# Sheet1.net
KiCad netlist of a schematic drawn in Altium Designer
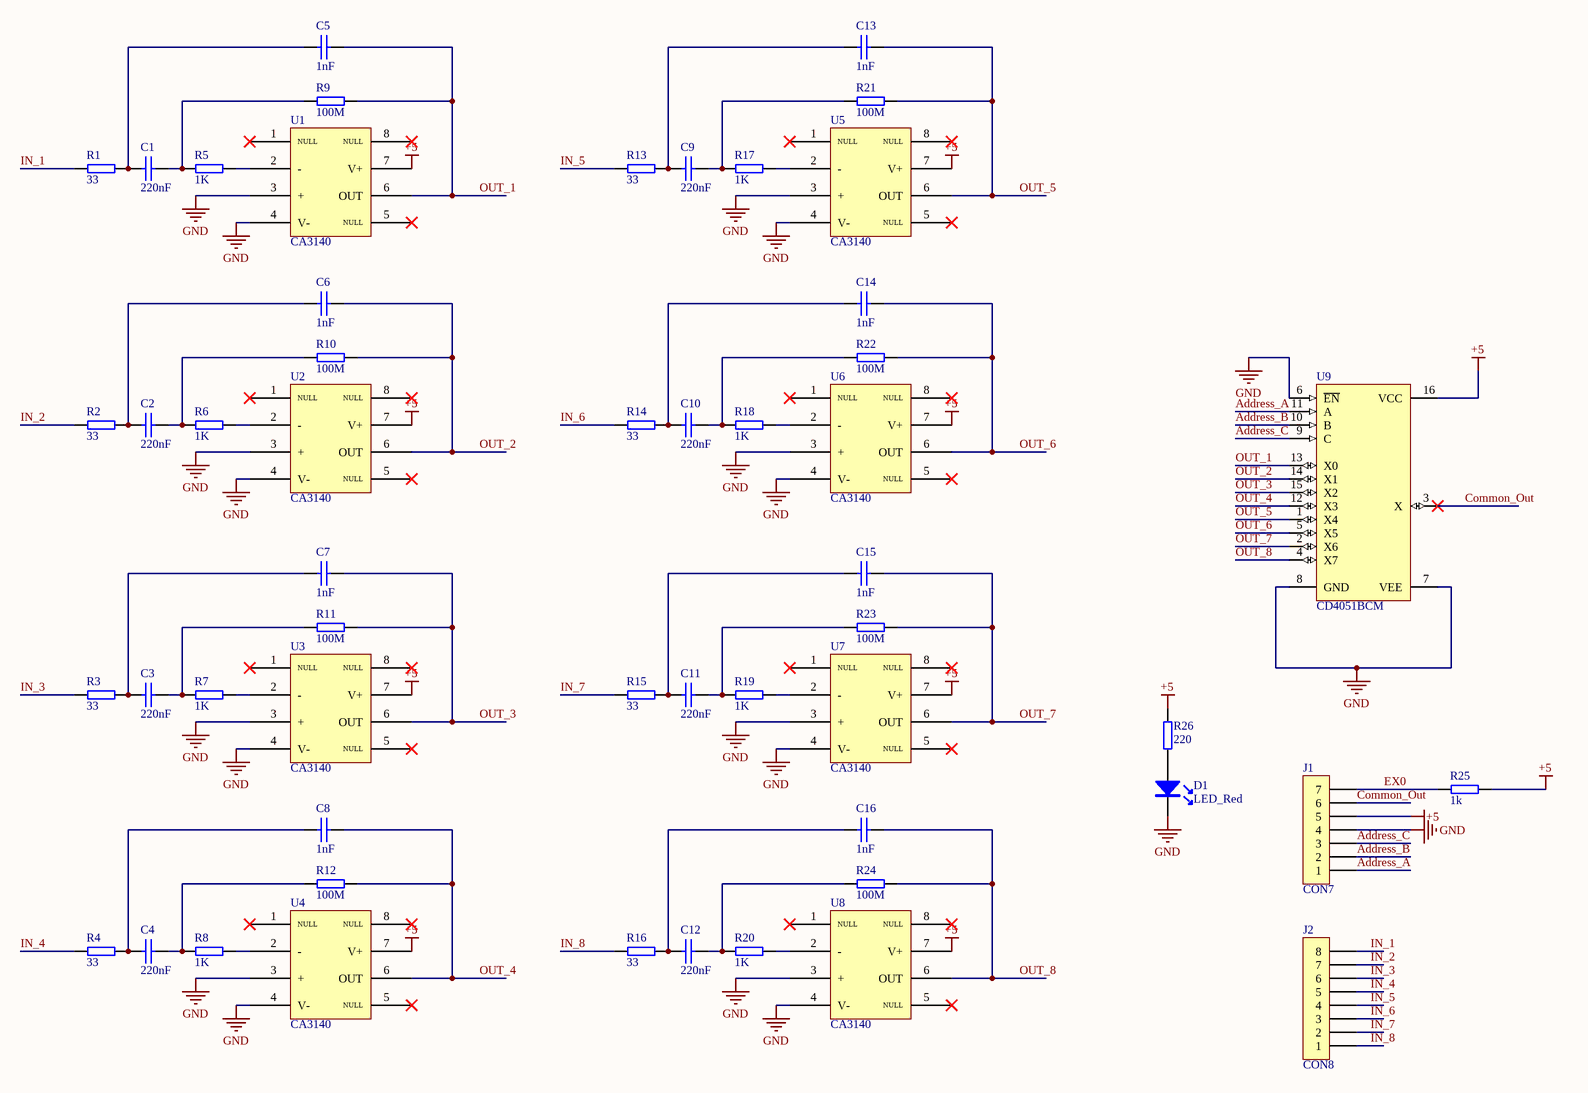
[diagram p0: Sheet1.SchDoc]

(export (version "E")
  (design (tool "Eeschema 10.0.6"))
  (components
    (comp (ref "C1")
      (value "220nF")
      (footprint "6-0805_L")
      (description "电容")
      (libsource (lib "Component") (part "CAP"))
    )
    (comp (ref "C2")
      (value "220nF")
      (footprint "6-0805_L")
      (description "电容")
      (libsource (lib "Component") (part "CAP"))
    )
    (comp (ref "C3")
      (value "220nF")
      (footprint "6-0805_L")
      (description "电容")
      (libsource (lib "Component") (part "CAP"))
    )
    (comp (ref "C4")
      (value "220nF")
      (footprint "6-0805_L")
      (description "电容")
      (libsource (lib "Component") (part "CAP"))
    )
    (comp (ref "C5")
      (value "1nF")
      (footprint "6-0805_L")
      (description "电容")
      (libsource (lib "Component") (part "CAP"))
    )
    (comp (ref "C6")
      (value "1nF")
      (footprint "6-0805_L")
      (description "电容")
      (libsource (lib "Component") (part "CAP"))
    )
    (comp (ref "C7")
      (value "1nF")
      (footprint "6-0805_L")
      (description "电容")
      (libsource (lib "Component") (part "CAP"))
    )
    (comp (ref "C8")
      (value "1nF")
      (footprint "6-0805_L")
      (description "电容")
      (libsource (lib "Component") (part "CAP"))
    )
    (comp (ref "C9")
      (value "220nF")
      (footprint "6-0805_L")
      (description "电容")
      (libsource (lib "Component") (part "CAP"))
    )
    (comp (ref "C10")
      (value "220nF")
      (footprint "6-0805_L")
      (description "电容")
      (libsource (lib "Component") (part "CAP"))
    )
    (comp (ref "C11")
      (value "220nF")
      (footprint "6-0805_L")
      (description "电容")
      (libsource (lib "Component") (part "CAP"))
    )
    (comp (ref "C12")
      (value "220nF")
      (footprint "6-0805_L")
      (description "电容")
      (libsource (lib "Component") (part "CAP"))
    )
    (comp (ref "C13")
      (value "1nF")
      (footprint "6-0805_L")
      (description "电容")
      (libsource (lib "Component") (part "CAP"))
    )
    (comp (ref "C14")
      (value "1nF")
      (footprint "6-0805_L")
      (description "电容")
      (libsource (lib "Component") (part "CAP"))
    )
    (comp (ref "C15")
      (value "1nF")
      (footprint "6-0805_L")
      (description "电容")
      (libsource (lib "Component") (part "CAP"))
    )
    (comp (ref "C16")
      (value "1nF")
      (footprint "6-0805_L")
      (description "电容")
      (libsource (lib "Component") (part "CAP"))
    )
    (comp (ref "D1")
      (value "LED_Red")
      (footprint "6-0805_M")
      (description "LED")
      (libsource (lib "Component") (part "LED"))
    )
    (comp (ref "J1")
      (value "CON7")
      (footprint "HDR1X7")
      (description "Connector")
      (libsource (lib "杂元件库") (part "CON7"))
    )
    (comp (ref "J2")
      (value "CON8")
      (footprint "XH2.54-8P")
      (description "连接器")
      (libsource (lib "Connector") (part "CON8"))
    )
    (comp (ref "R1")
      (value "33")
      (footprint "Miscellaneous Devices:6-0805_M")
      (description "电阻")
      (libsource (lib "Component") (part "RES"))
    )
    (comp (ref "R2")
      (value "33")
      (footprint "Miscellaneous Devices:6-0805_M")
      (description "电阻")
      (libsource (lib "Component") (part "RES"))
    )
    (comp (ref "R3")
      (value "33")
      (footprint "Miscellaneous Devices:6-0805_M")
      (description "电阻")
      (libsource (lib "Component") (part "RES"))
    )
    (comp (ref "R4")
      (value "33")
      (footprint "Miscellaneous Devices:6-0805_M")
      (description "电阻")
      (libsource (lib "Component") (part "RES"))
    )
    (comp (ref "R5")
      (value "1K")
      (footprint "6-0805_M")
      (description "电阻")
      (libsource (lib "Component") (part "RES"))
    )
    (comp (ref "R6")
      (value "1K")
      (footprint "6-0805_M")
      (description "电阻")
      (libsource (lib "Component") (part "RES"))
    )
    (comp (ref "R7")
      (value "1K")
      (footprint "6-0805_M")
      (description "电阻")
      (libsource (lib "Component") (part "RES"))
    )
    (comp (ref "R8")
      (value "1K")
      (footprint "6-0805_M")
      (description "电阻")
      (libsource (lib "Component") (part "RES"))
    )
    (comp (ref "R9")
      (value "100M")
      (footprint "Miscellaneous Devices:6-0805_M")
      (description "电阻")
      (libsource (lib "Component") (part "RES"))
    )
    (comp (ref "R10")
      (value "100M")
      (footprint "Miscellaneous Devices:6-0805_M")
      (description "电阻")
      (libsource (lib "Component") (part "RES"))
    )
    (comp (ref "R11")
      (value "100M")
      (footprint "Miscellaneous Devices:6-0805_M")
      (description "电阻")
      (libsource (lib "Component") (part "RES"))
    )
    (comp (ref "R12")
      (value "100M")
      (footprint "Miscellaneous Devices:6-0805_M")
      (description "电阻")
      (libsource (lib "Component") (part "RES"))
    )
    (comp (ref "R13")
      (value "33")
      (footprint "Miscellaneous Devices:6-0805_M")
      (description "电阻")
      (libsource (lib "Component") (part "RES"))
    )
    (comp (ref "R14")
      (value "33")
      (footprint "Miscellaneous Devices:6-0805_M")
      (description "电阻")
      (libsource (lib "Component") (part "RES"))
    )
    (comp (ref "R15")
      (value "33")
      (footprint "Miscellaneous Devices:6-0805_M")
      (description "电阻")
      (libsource (lib "Component") (part "RES"))
    )
    (comp (ref "R16")
      (value "33")
      (footprint "Miscellaneous Devices:6-0805_M")
      (description "电阻")
      (libsource (lib "Component") (part "RES"))
    )
    (comp (ref "R17")
      (value "1K")
      (footprint "6-0805_M")
      (description "电阻")
      (libsource (lib "Component") (part "RES"))
    )
    (comp (ref "R18")
      (value "1K")
      (footprint "6-0805_M")
      (description "电阻")
      (libsource (lib "Component") (part "RES"))
    )
    (comp (ref "R19")
      (value "1K")
      (footprint "6-0805_M")
      (description "电阻")
      (libsource (lib "Component") (part "RES"))
    )
    (comp (ref "R20")
      (value "1K")
      (footprint "6-0805_M")
      (description "电阻")
      (libsource (lib "Component") (part "RES"))
    )
    (comp (ref "R21")
      (value "100M")
      (footprint "Miscellaneous Devices:6-0805_M")
      (description "电阻")
      (libsource (lib "Component") (part "RES"))
    )
    (comp (ref "R22")
      (value "100M")
      (footprint "Miscellaneous Devices:6-0805_M")
      (description "电阻")
      (libsource (lib "Component") (part "RES"))
    )
    (comp (ref "R23")
      (value "100M")
      (footprint "Miscellaneous Devices:6-0805_M")
      (description "电阻")
      (libsource (lib "Component") (part "RES"))
    )
    (comp (ref "R24")
      (value "100M")
      (footprint "Miscellaneous Devices:6-0805_M")
      (description "电阻")
      (libsource (lib "Component") (part "RES"))
    )
    (comp (ref "R25")
      (value "1k")
      (footprint "6-0805_M")
      (description "电阻")
      (libsource (lib "Component") (part "RES"))
    )
    (comp (ref "R26")
      (value "220")
      (footprint "6-0805_M")
      (description "电阻")
      (libsource (lib "Component") (part "RES"))
    )
    (comp (ref "U1") (value "CA3140") (footprint "SO8_M") (libsource (lib "Mylib") (part "CA3140")))
    (comp (ref "U2") (value "CA3140") (footprint "SO8_M") (libsource (lib "Mylib") (part "CA3140")))
    (comp (ref "U3") (value "CA3140") (footprint "SO8_M") (libsource (lib "Mylib") (part "CA3140")))
    (comp (ref "U4") (value "CA3140") (footprint "SO8_M") (libsource (lib "Mylib") (part "CA3140")))
    (comp (ref "U5") (value "CA3140") (footprint "SO8_M") (libsource (lib "Mylib") (part "CA3140")))
    (comp (ref "U6") (value "CA3140") (footprint "SO8_M") (libsource (lib "Mylib") (part "CA3140")))
    (comp (ref "U7") (value "CA3140") (footprint "SO8_M") (libsource (lib "Mylib") (part "CA3140")))
    (comp (ref "U8") (value "CA3140") (footprint "SO8_M") (libsource (lib "Mylib") (part "CA3140")))
    (comp (ref "U9")
      (value "CD4051BCM")
      (footprint "M16A_N")
      (description "8-Channel Analog Multiplexer/Demultiplexer")
      (fields (field (name "PUBLISHER") "Altium Limited"))
      (libsource (lib "altium-import") (part "root_0_CD4051BCM_"))
    )
  )
  (nets
    (net (code "1") (name "+5") (class "Default")
      (node (ref "J1") (pin "5") (pinfunction "5_5") (pintype "passive"))
      (node (ref "R25") (pin "2") (pinfunction "2_2") (pintype "passive"))
      (node (ref "R26") (pin "2") (pinfunction "2_2") (pintype "passive"))
      (node (ref "U1") (pin "7") (pinfunction "V+_7") (pintype "passive"))
      (node (ref "U2") (pin "7") (pinfunction "V+_7") (pintype "passive"))
      (node (ref "U3") (pin "7") (pinfunction "V+_7") (pintype "passive"))
      (node (ref "U4") (pin "7") (pinfunction "V+_7") (pintype "passive"))
      (node (ref "U5") (pin "7") (pinfunction "V+_7") (pintype "passive"))
      (node (ref "U6") (pin "7") (pinfunction "V+_7") (pintype "passive"))
      (node (ref "U7") (pin "7") (pinfunction "V+_7") (pintype "passive"))
      (node (ref "U8") (pin "7") (pinfunction "V+_7") (pintype "passive"))
      (node (ref "U9") (pin "16") (pinfunction "VCC_16") (pintype "power_in"))
    )
    (net (code "2") (name "/Address_A") (class "Default")
      (node (ref "J1") (pin "1") (pinfunction "1_1") (pintype "passive"))
      (node (ref "U9") (pin "11") (pinfunction "A_11") (pintype "input"))
    )
    (net (code "3") (name "/Address_B") (class "Default")
      (node (ref "J1") (pin "2") (pinfunction "2_2") (pintype "passive"))
      (node (ref "U9") (pin "10") (pinfunction "B_10") (pintype "input"))
    )
    (net (code "4") (name "/Address_C") (class "Default")
      (node (ref "J1") (pin "3") (pinfunction "3_3") (pintype "passive"))
      (node (ref "U9") (pin "9") (pinfunction "C_9") (pintype "input"))
    )
    (net (code "5") (name "/Common_Out") (class "Default")
      (node (ref "J1") (pin "6") (pinfunction "6_6") (pintype "passive"))
      (node (ref "U9") (pin "3") (pinfunction "X_3") (pintype "bidirectional"))
    )
    (net (code "6") (name "/EX0") (class "Default")
      (node (ref "J1") (pin "7") (pinfunction "7_7") (pintype "passive"))
      (node (ref "R25") (pin "1") (pinfunction "1_1") (pintype "passive"))
    )
    (net (code "7") (name "/IN_1") (class "Default")
      (node (ref "J2") (pin "8") (pinfunction "8_8") (pintype "passive"))
      (node (ref "R1") (pin "1") (pinfunction "1_1") (pintype "passive"))
    )
    (net (code "8") (name "/IN_2") (class "Default")
      (node (ref "J2") (pin "7") (pinfunction "7_7") (pintype "passive"))
      (node (ref "R2") (pin "1") (pinfunction "1_1") (pintype "passive"))
    )
    (net (code "9") (name "/IN_3") (class "Default")
      (node (ref "J2") (pin "6") (pinfunction "6_6") (pintype "passive"))
      (node (ref "R3") (pin "1") (pinfunction "1_1") (pintype "passive"))
    )
    (net (code "10") (name "/IN_4") (class "Default")
      (node (ref "J2") (pin "5") (pinfunction "5_5") (pintype "passive"))
      (node (ref "R4") (pin "1") (pinfunction "1_1") (pintype "passive"))
    )
    (net (code "11") (name "/IN_5") (class "Default")
      (node (ref "J2") (pin "4") (pinfunction "4_4") (pintype "passive"))
      (node (ref "R13") (pin "1") (pinfunction "1_1") (pintype "passive"))
    )
    (net (code "12") (name "/IN_6") (class "Default")
      (node (ref "J2") (pin "3") (pinfunction "3_3") (pintype "passive"))
      (node (ref "R14") (pin "1") (pinfunction "1_1") (pintype "passive"))
    )
    (net (code "13") (name "/IN_7") (class "Default")
      (node (ref "J2") (pin "2") (pinfunction "2_2") (pintype "passive"))
      (node (ref "R15") (pin "1") (pinfunction "1_1") (pintype "passive"))
    )
    (net (code "14") (name "/IN_8") (class "Default")
      (node (ref "J2") (pin "1") (pinfunction "1_1") (pintype "passive"))
      (node (ref "R16") (pin "1") (pinfunction "1_1") (pintype "passive"))
    )
    (net (code "15") (name "/OUT_1") (class "Default")
      (node (ref "C5") (pin "2") (pinfunction "2_2") (pintype "passive"))
      (node (ref "R9") (pin "2") (pinfunction "2_2") (pintype "passive"))
      (node (ref "U1") (pin "6") (pinfunction "OUT_6") (pintype "passive"))
      (node (ref "U9") (pin "13") (pinfunction "X0_13") (pintype "bidirectional"))
    )
    (net (code "16") (name "/OUT_2") (class "Default")
      (node (ref "C6") (pin "2") (pinfunction "2_2") (pintype "passive"))
      (node (ref "R10") (pin "2") (pinfunction "2_2") (pintype "passive"))
      (node (ref "U2") (pin "6") (pinfunction "OUT_6") (pintype "passive"))
      (node (ref "U9") (pin "14") (pinfunction "X1_14") (pintype "bidirectional"))
    )
    (net (code "17") (name "/OUT_3") (class "Default")
      (node (ref "C7") (pin "2") (pinfunction "2_2") (pintype "passive"))
      (node (ref "R11") (pin "2") (pinfunction "2_2") (pintype "passive"))
      (node (ref "U3") (pin "6") (pinfunction "OUT_6") (pintype "passive"))
      (node (ref "U9") (pin "15") (pinfunction "X2_15") (pintype "bidirectional"))
    )
    (net (code "18") (name "/OUT_4") (class "Default")
      (node (ref "C8") (pin "2") (pinfunction "2_2") (pintype "passive"))
      (node (ref "R12") (pin "2") (pinfunction "2_2") (pintype "passive"))
      (node (ref "U4") (pin "6") (pinfunction "OUT_6") (pintype "passive"))
      (node (ref "U9") (pin "12") (pinfunction "X3_12") (pintype "bidirectional"))
    )
    (net (code "19") (name "/OUT_5") (class "Default")
      (node (ref "C13") (pin "2") (pinfunction "2_2") (pintype "passive"))
      (node (ref "R21") (pin "2") (pinfunction "2_2") (pintype "passive"))
      (node (ref "U5") (pin "6") (pinfunction "OUT_6") (pintype "passive"))
      (node (ref "U9") (pin "1") (pinfunction "X4_1") (pintype "bidirectional"))
    )
    (net (code "20") (name "/OUT_6") (class "Default")
      (node (ref "C14") (pin "2") (pinfunction "2_2") (pintype "passive"))
      (node (ref "R22") (pin "2") (pinfunction "2_2") (pintype "passive"))
      (node (ref "U6") (pin "6") (pinfunction "OUT_6") (pintype "passive"))
      (node (ref "U9") (pin "5") (pinfunction "X5_5") (pintype "bidirectional"))
    )
    (net (code "21") (name "/OUT_7") (class "Default")
      (node (ref "C15") (pin "2") (pinfunction "2_2") (pintype "passive"))
      (node (ref "R23") (pin "2") (pinfunction "2_2") (pintype "passive"))
      (node (ref "U7") (pin "6") (pinfunction "OUT_6") (pintype "passive"))
      (node (ref "U9") (pin "2") (pinfunction "X6_2") (pintype "bidirectional"))
    )
    (net (code "22") (name "/OUT_8") (class "Default")
      (node (ref "C16") (pin "2") (pinfunction "2_2") (pintype "passive"))
      (node (ref "R24") (pin "2") (pinfunction "2_2") (pintype "passive"))
      (node (ref "U8") (pin "6") (pinfunction "OUT_6") (pintype "passive"))
      (node (ref "U9") (pin "4") (pinfunction "X7_4") (pintype "bidirectional"))
    )
    (net (code "23") (name "GND") (class "Default")
      (node (ref "D1") (pin "2") (pinfunction "2_2") (pintype "passive"))
      (node (ref "J1") (pin "4") (pinfunction "4_4") (pintype "passive"))
      (node (ref "U1") (pin "3") (pinfunction "+_3") (pintype "passive"))
      (node (ref "U1") (pin "4") (pinfunction "V-_4") (pintype "passive"))
      (node (ref "U2") (pin "3") (pinfunction "+_3") (pintype "passive"))
      (node (ref "U2") (pin "4") (pinfunction "V-_4") (pintype "passive"))
      (node (ref "U3") (pin "3") (pinfunction "+_3") (pintype "passive"))
      (node (ref "U3") (pin "4") (pinfunction "V-_4") (pintype "passive"))
      (node (ref "U4") (pin "3") (pinfunction "+_3") (pintype "passive"))
      (node (ref "U4") (pin "4") (pinfunction "V-_4") (pintype "passive"))
      (node (ref "U5") (pin "3") (pinfunction "+_3") (pintype "passive"))
      (node (ref "U5") (pin "4") (pinfunction "V-_4") (pintype "passive"))
      (node (ref "U6") (pin "3") (pinfunction "+_3") (pintype "passive"))
      (node (ref "U6") (pin "4") (pinfunction "V-_4") (pintype "passive"))
      (node (ref "U7") (pin "3") (pinfunction "+_3") (pintype "passive"))
      (node (ref "U7") (pin "4") (pinfunction "V-_4") (pintype "passive"))
      (node (ref "U8") (pin "3") (pinfunction "+_3") (pintype "passive"))
      (node (ref "U8") (pin "4") (pinfunction "V-_4") (pintype "passive"))
      (node (ref "U9") (pin "6") (pinfunction "~{EN}_6") (pintype "input"))
      (node (ref "U9") (pin "7") (pinfunction "VEE_7") (pintype "power_in"))
      (node (ref "U9") (pin "8") (pinfunction "GND_8") (pintype "power_in"))
    )
    (net (code "24") (name "Net-(C1-Pad1)") (class "Default")
      (node (ref "C1") (pin "1") (pinfunction "1_1") (pintype "passive"))
      (node (ref "C5") (pin "1") (pinfunction "1_1") (pintype "passive"))
      (node (ref "R1") (pin "2") (pinfunction "2_2") (pintype "passive"))
    )
    (net (code "25") (name "Net-(C1-Pad2)") (class "Default")
      (node (ref "C1") (pin "2") (pinfunction "2_2") (pintype "passive"))
      (node (ref "R5") (pin "1") (pinfunction "1_1") (pintype "passive"))
      (node (ref "R9") (pin "1") (pinfunction "1_1") (pintype "passive"))
    )
    (net (code "26") (name "Net-(C2-Pad1)") (class "Default")
      (node (ref "C2") (pin "1") (pinfunction "1_1") (pintype "passive"))
      (node (ref "C6") (pin "1") (pinfunction "1_1") (pintype "passive"))
      (node (ref "R2") (pin "2") (pinfunction "2_2") (pintype "passive"))
    )
    (net (code "27") (name "Net-(C2-Pad2)") (class "Default")
      (node (ref "C2") (pin "2") (pinfunction "2_2") (pintype "passive"))
      (node (ref "R10") (pin "1") (pinfunction "1_1") (pintype "passive"))
      (node (ref "R6") (pin "1") (pinfunction "1_1") (pintype "passive"))
    )
    (net (code "28") (name "Net-(C3-Pad1)") (class "Default")
      (node (ref "C3") (pin "1") (pinfunction "1_1") (pintype "passive"))
      (node (ref "C7") (pin "1") (pinfunction "1_1") (pintype "passive"))
      (node (ref "R3") (pin "2") (pinfunction "2_2") (pintype "passive"))
    )
    (net (code "29") (name "Net-(C3-Pad2)") (class "Default")
      (node (ref "C3") (pin "2") (pinfunction "2_2") (pintype "passive"))
      (node (ref "R11") (pin "1") (pinfunction "1_1") (pintype "passive"))
      (node (ref "R7") (pin "1") (pinfunction "1_1") (pintype "passive"))
    )
    (net (code "30") (name "Net-(C4-Pad1)") (class "Default")
      (node (ref "C4") (pin "1") (pinfunction "1_1") (pintype "passive"))
      (node (ref "C8") (pin "1") (pinfunction "1_1") (pintype "passive"))
      (node (ref "R4") (pin "2") (pinfunction "2_2") (pintype "passive"))
    )
    (net (code "31") (name "Net-(C4-Pad2)") (class "Default")
      (node (ref "C4") (pin "2") (pinfunction "2_2") (pintype "passive"))
      (node (ref "R12") (pin "1") (pinfunction "1_1") (pintype "passive"))
      (node (ref "R8") (pin "1") (pinfunction "1_1") (pintype "passive"))
    )
    (net (code "32") (name "Net-(C9-Pad2)") (class "Default")
      (node (ref "C9") (pin "2") (pinfunction "2_2") (pintype "passive"))
      (node (ref "R17") (pin "1") (pinfunction "1_1") (pintype "passive"))
      (node (ref "R21") (pin "1") (pinfunction "1_1") (pintype "passive"))
    )
    (net (code "33") (name "Net-(C10-Pad1)") (class "Default")
      (node (ref "C10") (pin "1") (pinfunction "1_1") (pintype "passive"))
      (node (ref "C14") (pin "1") (pinfunction "1_1") (pintype "passive"))
      (node (ref "R14") (pin "2") (pinfunction "2_2") (pintype "passive"))
    )
    (net (code "34") (name "Net-(C10-Pad2)") (class "Default")
      (node (ref "C10") (pin "2") (pinfunction "2_2") (pintype "passive"))
      (node (ref "R18") (pin "1") (pinfunction "1_1") (pintype "passive"))
      (node (ref "R22") (pin "1") (pinfunction "1_1") (pintype "passive"))
    )
    (net (code "35") (name "Net-(C11-Pad1)") (class "Default")
      (node (ref "C11") (pin "1") (pinfunction "1_1") (pintype "passive"))
      (node (ref "C15") (pin "1") (pinfunction "1_1") (pintype "passive"))
      (node (ref "R15") (pin "2") (pinfunction "2_2") (pintype "passive"))
    )
    (net (code "36") (name "Net-(C11-Pad2)") (class "Default")
      (node (ref "C11") (pin "2") (pinfunction "2_2") (pintype "passive"))
      (node (ref "R19") (pin "1") (pinfunction "1_1") (pintype "passive"))
      (node (ref "R23") (pin "1") (pinfunction "1_1") (pintype "passive"))
    )
    (net (code "37") (name "Net-(C12-Pad1)") (class "Default")
      (node (ref "C12") (pin "1") (pinfunction "1_1") (pintype "passive"))
      (node (ref "C16") (pin "1") (pinfunction "1_1") (pintype "passive"))
      (node (ref "R16") (pin "2") (pinfunction "2_2") (pintype "passive"))
    )
    (net (code "38") (name "Net-(C12-Pad2)") (class "Default")
      (node (ref "C12") (pin "2") (pinfunction "2_2") (pintype "passive"))
      (node (ref "R20") (pin "1") (pinfunction "1_1") (pintype "passive"))
      (node (ref "R24") (pin "1") (pinfunction "1_1") (pintype "passive"))
    )
    (net (code "39") (name "Net-(C13-Pad1)") (class "Default")
      (node (ref "C13") (pin "1") (pinfunction "1_1") (pintype "passive"))
      (node (ref "C9") (pin "1") (pinfunction "1_1") (pintype "passive"))
      (node (ref "R13") (pin "2") (pinfunction "2_2") (pintype "passive"))
    )
    (net (code "40") (name "Net-(D1-Pad1)") (class "Default")
      (node (ref "D1") (pin "1") (pinfunction "1_1") (pintype "passive"))
      (node (ref "R26") (pin "1") (pinfunction "1_1") (pintype "passive"))
    )
    (net (code "41") (name "Net-(U1--)") (class "Default")
      (node (ref "R5") (pin "2") (pinfunction "2_2") (pintype "passive"))
      (node (ref "U1") (pin "2") (pinfunction "-_2") (pintype "passive"))
    )
    (net (code "42") (name "Net-(U2--)") (class "Default")
      (node (ref "R6") (pin "2") (pinfunction "2_2") (pintype "passive"))
      (node (ref "U2") (pin "2") (pinfunction "-_2") (pintype "passive"))
    )
    (net (code "43") (name "Net-(U3--)") (class "Default")
      (node (ref "R7") (pin "2") (pinfunction "2_2") (pintype "passive"))
      (node (ref "U3") (pin "2") (pinfunction "-_2") (pintype "passive"))
    )
    (net (code "44") (name "Net-(U4--)") (class "Default")
      (node (ref "R8") (pin "2") (pinfunction "2_2") (pintype "passive"))
      (node (ref "U4") (pin "2") (pinfunction "-_2") (pintype "passive"))
    )
    (net (code "45") (name "Net-(U5--)") (class "Default")
      (node (ref "R17") (pin "2") (pinfunction "2_2") (pintype "passive"))
      (node (ref "U5") (pin "2") (pinfunction "-_2") (pintype "passive"))
    )
    (net (code "46") (name "Net-(U6--)") (class "Default")
      (node (ref "R18") (pin "2") (pinfunction "2_2") (pintype "passive"))
      (node (ref "U6") (pin "2") (pinfunction "-_2") (pintype "passive"))
    )
    (net (code "47") (name "Net-(U7--)") (class "Default")
      (node (ref "R19") (pin "2") (pinfunction "2_2") (pintype "passive"))
      (node (ref "U7") (pin "2") (pinfunction "-_2") (pintype "passive"))
    )
    (net (code "48") (name "Net-(U8--)") (class "Default")
      (node (ref "R20") (pin "2") (pinfunction "2_2") (pintype "passive"))
      (node (ref "U8") (pin "2") (pinfunction "-_2") (pintype "passive"))
    )
    (net (code "49") (name "unconnected-(U1-NULL-Pad1)") (class "Default")
      (node (ref "U1") (pin "1") (pinfunction "NULL_1") (pintype "passive+no_connect"))
    )
    (net (code "50") (name "unconnected-(U1-NULL-Pad5)") (class "Default")
      (node (ref "U1") (pin "5") (pinfunction "NULL_5") (pintype "passive+no_connect"))
    )
    (net (code "51") (name "unconnected-(U1-NULL-Pad8)") (class "Default")
      (node (ref "U1") (pin "8") (pinfunction "NULL_8") (pintype "passive+no_connect"))
    )
    (net (code "52") (name "unconnected-(U2-NULL-Pad1)") (class "Default")
      (node (ref "U2") (pin "1") (pinfunction "NULL_1") (pintype "passive+no_connect"))
    )
    (net (code "53") (name "unconnected-(U2-NULL-Pad5)") (class "Default")
      (node (ref "U2") (pin "5") (pinfunction "NULL_5") (pintype "passive+no_connect"))
    )
    (net (code "54") (name "unconnected-(U2-NULL-Pad8)") (class "Default")
      (node (ref "U2") (pin "8") (pinfunction "NULL_8") (pintype "passive+no_connect"))
    )
    (net (code "55") (name "unconnected-(U3-NULL-Pad1)") (class "Default")
      (node (ref "U3") (pin "1") (pinfunction "NULL_1") (pintype "passive+no_connect"))
    )
    (net (code "56") (name "unconnected-(U3-NULL-Pad5)") (class "Default")
      (node (ref "U3") (pin "5") (pinfunction "NULL_5") (pintype "passive+no_connect"))
    )
    (net (code "57") (name "unconnected-(U3-NULL-Pad8)") (class "Default")
      (node (ref "U3") (pin "8") (pinfunction "NULL_8") (pintype "passive+no_connect"))
    )
    (net (code "58") (name "unconnected-(U4-NULL-Pad1)") (class "Default")
      (node (ref "U4") (pin "1") (pinfunction "NULL_1") (pintype "passive+no_connect"))
    )
    (net (code "59") (name "unconnected-(U4-NULL-Pad5)") (class "Default")
      (node (ref "U4") (pin "5") (pinfunction "NULL_5") (pintype "passive+no_connect"))
    )
    (net (code "60") (name "unconnected-(U4-NULL-Pad8)") (class "Default")
      (node (ref "U4") (pin "8") (pinfunction "NULL_8") (pintype "passive+no_connect"))
    )
    (net (code "61") (name "unconnected-(U5-NULL-Pad1)") (class "Default")
      (node (ref "U5") (pin "1") (pinfunction "NULL_1") (pintype "passive+no_connect"))
    )
    (net (code "62") (name "unconnected-(U5-NULL-Pad5)") (class "Default")
      (node (ref "U5") (pin "5") (pinfunction "NULL_5") (pintype "passive+no_connect"))
    )
    (net (code "63") (name "unconnected-(U5-NULL-Pad8)") (class "Default")
      (node (ref "U5") (pin "8") (pinfunction "NULL_8") (pintype "passive+no_connect"))
    )
    (net (code "64") (name "unconnected-(U6-NULL-Pad1)") (class "Default")
      (node (ref "U6") (pin "1") (pinfunction "NULL_1") (pintype "passive+no_connect"))
    )
    (net (code "65") (name "unconnected-(U6-NULL-Pad5)") (class "Default")
      (node (ref "U6") (pin "5") (pinfunction "NULL_5") (pintype "passive+no_connect"))
    )
    (net (code "66") (name "unconnected-(U6-NULL-Pad8)") (class "Default")
      (node (ref "U6") (pin "8") (pinfunction "NULL_8") (pintype "passive+no_connect"))
    )
    (net (code "67") (name "unconnected-(U7-NULL-Pad1)") (class "Default")
      (node (ref "U7") (pin "1") (pinfunction "NULL_1") (pintype "passive+no_connect"))
    )
    (net (code "68") (name "unconnected-(U7-NULL-Pad5)") (class "Default")
      (node (ref "U7") (pin "5") (pinfunction "NULL_5") (pintype "passive+no_connect"))
    )
    (net (code "69") (name "unconnected-(U7-NULL-Pad8)") (class "Default")
      (node (ref "U7") (pin "8") (pinfunction "NULL_8") (pintype "passive+no_connect"))
    )
    (net (code "70") (name "unconnected-(U8-NULL-Pad1)") (class "Default")
      (node (ref "U8") (pin "1") (pinfunction "NULL_1") (pintype "passive+no_connect"))
    )
    (net (code "71") (name "unconnected-(U8-NULL-Pad5)") (class "Default")
      (node (ref "U8") (pin "5") (pinfunction "NULL_5") (pintype "passive+no_connect"))
    )
    (net (code "72") (name "unconnected-(U8-NULL-Pad8)") (class "Default")
      (node (ref "U8") (pin "8") (pinfunction "NULL_8") (pintype "passive+no_connect"))
    )
  )
)
